# LiBatteryChargeBoostBoard.net
KiCad netlist of a schematic drawn in EAGLE
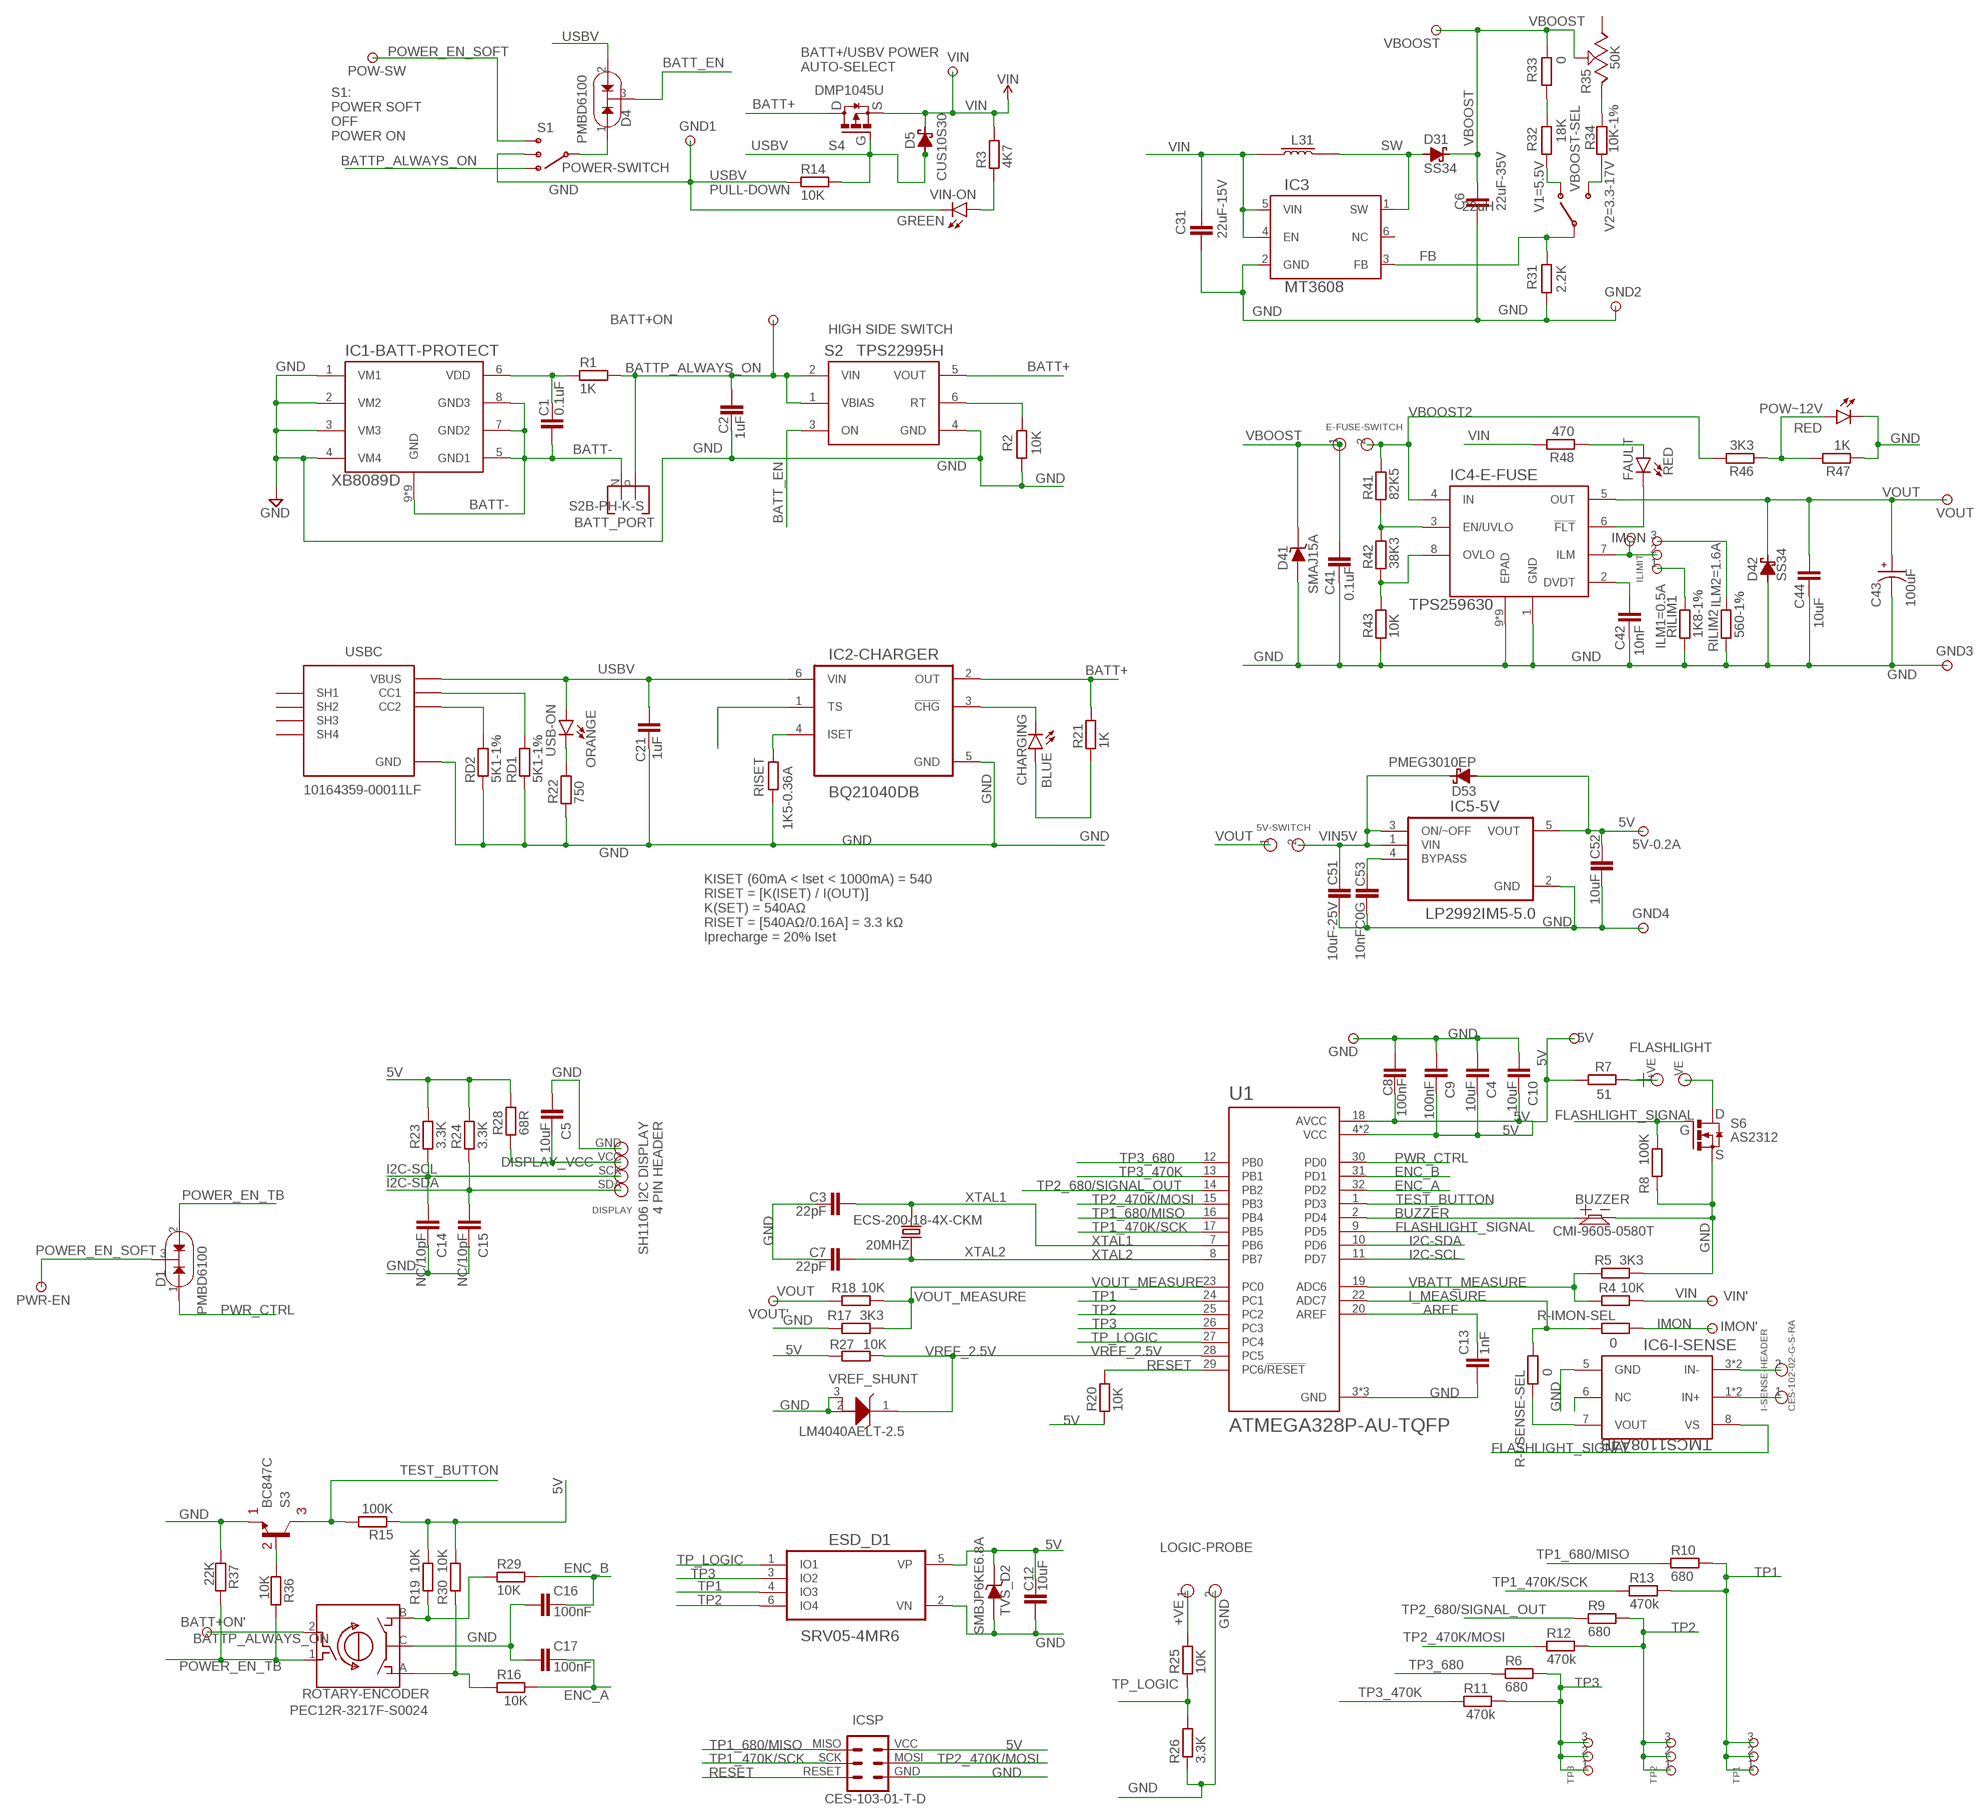
[diagram p0: schematic, sheet 1]

(export (version "E")
  (design (tool "Eeschema 10.0.6"))
  (components
    (comp (ref "5V")
      (value "TEST-POINT-TH")
      (footprint "eagle-import:TEST-POINT-TH-1MM")
      (libsource (lib "eagle-import") (part "TEST-POINT-TH"))
    )
    (comp (ref "5V-0.2A")
      (value "TEST-POINT-TH")
      (footprint "eagle-import:TEST-POINT-TH-1MM")
      (libsource (lib "eagle-import") (part "TEST-POINT-TH"))
    )
    (comp (ref "5V-SWITCH")
      (value "HEADER-2PIN-0.1\"P")
      (footprint "eagle-import:HEADER-2PIN-0.1_P")
      (libsource (lib "eagle-import") (part "HEADER-2PIN-0.1{dblquote}P"))
    )
    (comp (ref "20MHZ")
      (value "ECS-200-18-4X-CKM")
      (footprint "eagle-import:XTAL_ECS-200-18-4X-CKM")
      (fields (field (name "MF") "ECS Inc."))
      (libsource (lib "eagle-import") (part "CRYSTAL-20MHZ-ECS-200-18-4X-CKM"))
    )
    (comp (ref "BATT+ON")
      (value "TEST-POINT-TH")
      (footprint "eagle-import:TEST-POINT-TH-1MM")
      (libsource (lib "eagle-import") (part "TEST-POINT-TH"))
    )
    (comp (ref "BATT+ON'")
      (value "TEST-POINT-TH")
      (footprint "eagle-import:TEST-POINT-TH-1MM")
      (libsource (lib "eagle-import") (part "TEST-POINT-TH"))
    )
    (comp (ref "BATT_PORT")
      (value "S2B-PH-K-S")
      (footprint "eagle-import:S2B-PH-K-S")
      (libsource (lib "eagle-import") (part "S2B-PH-K-S"))
    )
    (comp (ref "BUZZER")
      (value "CMI-9605-0580T")
      (footprint "eagle-import:BUZZER-ACTIVE-CMI-9605-0580T")
      (libsource (lib "eagle-import") (part "BUZZER-ACTIVE-CMI-9605-0580T"))
    )
    (comp (ref "C1")
      (value "0.1uF")
      (footprint "eagle-import:0603")
      (libsource (lib "eagle-import") (part "CAPACITOR_SMD0603"))
    )
    (comp (ref "C2")
      (value "1uF")
      (footprint "eagle-import:0603")
      (libsource (lib "eagle-import") (part "CAPACITOR_SMD0603"))
    )
    (comp (ref "C3")
      (value "22pF")
      (footprint "eagle-import:0603")
      (libsource (lib "eagle-import") (part "CAPACITOR_SMD0603"))
    )
    (comp (ref "C4")
      (value "10uF")
      (footprint "eagle-import:0603")
      (libsource (lib "eagle-import") (part "CAPACITOR_SMD0603"))
    )
    (comp (ref "C5")
      (value "10uF")
      (footprint "eagle-import:1206")
      (libsource (lib "eagle-import") (part "CAPACITOR1206"))
    )
    (comp (ref "C6")
      (value "22uF-35V")
      (footprint "eagle-import:1206")
      (libsource (lib "eagle-import") (part "CAPACITOR_SMD1206"))
    )
    (comp (ref "C7")
      (value "22pF")
      (footprint "eagle-import:0603")
      (libsource (lib "eagle-import") (part "CAPACITOR_SMD0603"))
    )
    (comp (ref "C8")
      (value "100nF")
      (footprint "eagle-import:0603")
      (libsource (lib "eagle-import") (part "CAPACITOR_SMD0603"))
    )
    (comp (ref "C9")
      (value "100nF")
      (footprint "eagle-import:0603")
      (libsource (lib "eagle-import") (part "CAPACITOR_SMD0603"))
    )
    (comp (ref "C10")
      (value "10uF")
      (footprint "eagle-import:0603")
      (libsource (lib "eagle-import") (part "CAPACITOR_SMD0603"))
    )
    (comp (ref "C12")
      (value "10uF")
      (footprint "eagle-import:0603")
      (libsource (lib "eagle-import") (part "CAPACITOR_SMD0603"))
    )
    (comp (ref "C13")
      (value "1nF")
      (footprint "eagle-import:0603")
      (libsource (lib "eagle-import") (part "CAPACITOR_SMD0603"))
    )
    (comp (ref "C14")
      (value "NC/10pF")
      (footprint "eagle-import:0603")
      (libsource (lib "eagle-import") (part "CAPACITOR_SMD0603"))
    )
    (comp (ref "C15")
      (value "NC/10pF")
      (footprint "eagle-import:0603")
      (libsource (lib "eagle-import") (part "CAPACITOR_SMD0603"))
    )
    (comp (ref "C16")
      (value "100nF")
      (footprint "eagle-import:0603")
      (libsource (lib "eagle-import") (part "CAPACITOR_SMD0603"))
    )
    (comp (ref "C17")
      (value "100nF")
      (footprint "eagle-import:0603")
      (libsource (lib "eagle-import") (part "CAPACITOR_SMD0603"))
    )
    (comp (ref "C21")
      (value "1uF")
      (footprint "eagle-import:0603")
      (libsource (lib "eagle-import") (part "CAPACITOR_SMD0603"))
    )
    (comp (ref "C31")
      (value "22uF-15V")
      (footprint "eagle-import:1206")
      (libsource (lib "eagle-import") (part "CAPACITOR_SMD1206"))
    )
    (comp (ref "C41")
      (value "0.1uF")
      (footprint "eagle-import:0603")
      (libsource (lib "eagle-import") (part "CAPACITOR_SMD0603"))
    )
    (comp (ref "C42")
      (value "10nF")
      (footprint "eagle-import:0603")
      (libsource (lib "eagle-import") (part "CAPACITOR_SMD0603"))
    )
    (comp (ref "C43")
      (value "100uF")
      (footprint "eagle-import:CAP_EEEFN1E101UP")
      (fields (field (name "MF") "Panasonic Electronic Components") (field (name "MP") "EEE-FN1E101UP"))
      (libsource (lib "eagle-import") (part "EEEFN1E101UP"))
    )
    (comp (ref "C44")
      (value "10uF")
      (footprint "eagle-import:0603")
      (libsource (lib "eagle-import") (part "CAPACITOR_SMD0603"))
    )
    (comp (ref "C51")
      (value "10uF-25V")
      (footprint "eagle-import:0603")
      (libsource (lib "eagle-import") (part "CAPACITOR0603"))
    )
    (comp (ref "C52")
      (value "10uF")
      (footprint "eagle-import:0603")
      (libsource (lib "eagle-import") (part "CAPACITOR0603"))
    )
    (comp (ref "C53")
      (value "10nFC0G")
      (footprint "eagle-import:0603")
      (libsource (lib "eagle-import") (part "CAPACITOR_SMD0603"))
    )
    (comp (ref "CHARGING")
      (value "BLUE")
      (footprint "eagle-import:0603-DIODE")
      (libsource (lib "eagle-import") (part "LED0603"))
    )
    (comp (ref "D1")
      (value "PMBD6100")
      (footprint "eagle-import:SOT-23-3")
      (libsource (lib "eagle-import") (part "DIODE-DOUBLE-COMMON-CATHODE-PMBD6100,215"))
    )
    (comp (ref "D4")
      (value "PMBD6100")
      (footprint "eagle-import:SOT-23-3")
      (libsource (lib "eagle-import") (part "DIODE-DOUBLE-COMMON-CATHODE-PMBD6100,215"))
    )
    (comp (ref "D5")
      (value "CUS10S30")
      (footprint "eagle-import:SOD-323")
      (libsource (lib "eagle-import") (part "DIODE-SCHOTTKY-CUS10S30,H3F"))
    )
    (comp (ref "D31")
      (value "SS34")
      (footprint "eagle-import:SMA")
      (libsource (lib "eagle-import") (part "DIODE-SCHOTTKY-SS34"))
    )
    (comp (ref "D41")
      (value "SMAJ15A")
      (footprint "eagle-import:SMA")
      (libsource (lib "eagle-import") (part "DIODE-TVS-SMA"))
    )
    (comp (ref "D42")
      (value "SS34")
      (footprint "eagle-import:SMA")
      (libsource (lib "eagle-import") (part "DIODE-SCHOTTKY-SS34"))
    )
    (comp (ref "D53")
      (value "PMEG3010EP")
      (footprint "eagle-import:SOD-128")
      (libsource (lib "eagle-import") (part "DIODE-SCHOTTKY-PMEG3010EP,115"))
    )
    (comp (ref "DISPLAY")
      (value "DISPLAY-1.3\"-SH1106-I2C")
      (footprint "eagle-import:DISPLAY-1.3_-SH1106-I2C")
      (libsource (lib "eagle-import") (part "DISPLAY-1.3{dblquote}-SH1106-I2C"))
    )
    (comp (ref "E-FUSE-SWITCH")
      (value "HEADER-2PIN-0.1\"P")
      (footprint "eagle-import:HEADER-2PIN-0.1_P")
      (libsource (lib "eagle-import") (part "HEADER-2PIN-0.1{dblquote}P"))
    )
    (comp (ref "ESD_D1")
      (value "SRV05-4MR6")
      (footprint "eagle-import:SOT-23-6")
      (fields (field (name "MF") "ON Semiconductor") (field (name "MP") "SRV05-4MR6T1G"))
      (libsource (lib "eagle-import") (part "SRV05-4MR6T1G"))
    )
    (comp (ref "FAULT")
      (value "RED")
      (footprint "eagle-import:0603-DIODE")
      (libsource (lib "eagle-import") (part "LED0603"))
    )
    (comp (ref "FLASHLIGHT")
      (value "HEADER-2PIN-0.2\"P")
      (footprint "eagle-import:HEADER-2PIN-0.2_P")
      (libsource (lib "eagle-import") (part "HEADER-2PIN-0.2{dblquote}P"))
    )
    (comp (ref "GND")
      (value "TEST-POINT-TH")
      (footprint "eagle-import:TEST-POINT-TH-1MM")
      (libsource (lib "eagle-import") (part "TEST-POINT-TH"))
    )
    (comp (ref "GND1")
      (value "TEST-POINT-TH")
      (footprint "eagle-import:TEST-POINT-TH-1MM")
      (libsource (lib "eagle-import") (part "TEST-POINT-TH"))
    )
    (comp (ref "GND2")
      (value "TEST-POINT-TH")
      (footprint "eagle-import:TEST-POINT-TH-1MM")
      (libsource (lib "eagle-import") (part "TEST-POINT-TH"))
    )
    (comp (ref "GND3")
      (value "TEST-POINT-TH")
      (footprint "eagle-import:TEST-POINT-TH-1MM")
      (libsource (lib "eagle-import") (part "TEST-POINT-TH"))
    )
    (comp (ref "GND4")
      (value "TEST-POINT-TH")
      (footprint "eagle-import:TEST-POINT-TH-1MM")
      (libsource (lib "eagle-import") (part "TEST-POINT-TH"))
    )
    (comp (ref "I-SENSE-HEADER")
      (value "CES-102-02-G-S-RA")
      (footprint "eagle-import:HEADER-2PIN-0.1_P")
      (libsource (lib "eagle-import") (part "HEADER-2PIN-0.1{dblquote}P"))
    )
    (comp (ref "IC1-BATT-PROTECT")
      (value "XB8089D")
      (footprint "eagle-import:SOIC-8-POWER-PAD")
      (libsource (lib "eagle-import") (part "XB8089D"))
    )
    (comp (ref "IC2-CHARGER")
      (value "BQ21040DB")
      (footprint "eagle-import:SOT-23-6")
      (fields (field (name "MF") "Texas Instruments") (field (name "MP") "BQ21040DBVR"))
      (libsource (lib "eagle-import") (part "BQ21040DBVR"))
    )
    (comp (ref "IC3")
      (value "MT3608")
      (footprint "eagle-import:SOT-23-6")
      (libsource (lib "eagle-import") (part "MT3608"))
    )
    (comp (ref "IC4-E-FUSE")
      (value "TPS259630")
      (footprint "eagle-import:SOIC-8-POWER-PAD")
      (libsource (lib "eagle-import") (part "TPS259621DDAR"))
    )
    (comp (ref "IC5-5V")
      (value "LP2992IM5-5.0")
      (footprint "eagle-import:SOT-23-5")
      (fields (field (name "MF") "Texas Instruments") (field (name "MP") "LP2992IM5-5.0/NOPB"))
      (libsource (lib "eagle-import") (part "LP2992IM5-5.0"))
    )
    (comp (ref "IC6-I-SENSE")
      (value "TMCS1108A4B")
      (footprint "eagle-import:SOIC-8")
      (libsource (lib "eagle-import") (part "TMCS1108A4B-CURRENT-SENSE"))
    )
    (comp (ref "ICSP")
      (value "CES-103-01-T-D")
      (footprint "eagle-import:HEADER-ICSP-0.1_P")
      (libsource (lib "eagle-import") (part "HEADER-ICSP-0.1{dblquote}P"))
    )
    (comp (ref "ILIMIT")
      (value "HEADER-3PIN-0.1\"P")
      (footprint "eagle-import:HEADER-3PIN-0.1_P")
      (libsource (lib "eagle-import") (part "HEADER-3PIN-0.1{dblquote}P"))
    )
    (comp (ref "IMON")
      (value "TEST-POINT-TH")
      (footprint "eagle-import:TEST-POINT-TH-1MM")
      (libsource (lib "eagle-import") (part "TEST-POINT-TH"))
    )
    (comp (ref "IMON'")
      (value "TEST-POINT-TH")
      (footprint "eagle-import:TEST-POINT-TH-1MM")
      (libsource (lib "eagle-import") (part "TEST-POINT-TH"))
    )
    (comp (ref "L31")
      (value "22uH")
      (footprint "eagle-import:INDUCTOR-SMRH74-220MT")
      (libsource (lib "eagle-import") (part "INDUCTOR-SMRH74-220MT"))
    )
    (comp (ref "LOGIC-PROBE")
      (value "HEADER-2PIN-0.1\"P")
      (footprint "eagle-import:HEADER-2PIN-0.1_P")
      (libsource (lib "eagle-import") (part "HEADER-2PIN-0.1{dblquote}P"))
    )
    (comp (ref "POW-SW")
      (value "TEST-POINT-TH")
      (footprint "eagle-import:TEST-POINT-TH-1MM")
      (libsource (lib "eagle-import") (part "TEST-POINT-TH"))
    )
    (comp (ref "POW~12V")
      (value "RED")
      (footprint "eagle-import:1206-DIODE")
      (libsource (lib "eagle-import") (part "LED1206"))
    )
    (comp (ref "PWR-EN")
      (value "TEST-POINT-TH")
      (footprint "eagle-import:TEST-POINT-TH-1MM")
      (libsource (lib "eagle-import") (part "TEST-POINT-TH"))
    )
    (comp (ref "R-I-SENSE-SEL")
      (value "0")
      (footprint "eagle-import:0603")
      (libsource (lib "eagle-import") (part "RESISTOR_SMD0603"))
    )
    (comp (ref "R-IMON-SEL")
      (value "0")
      (footprint "eagle-import:0603")
      (libsource (lib "eagle-import") (part "RESISTOR_SMD0603"))
    )
    (comp (ref "R1")
      (value "1K")
      (footprint "eagle-import:0603")
      (libsource (lib "eagle-import") (part "RESISTOR_SMD0603"))
    )
    (comp (ref "R2")
      (value "10K")
      (footprint "eagle-import:0603")
      (libsource (lib "eagle-import") (part "RESISTOR_SMD0603"))
    )
    (comp (ref "R3")
      (value "4K7")
      (footprint "eagle-import:0603")
      (libsource (lib "eagle-import") (part "RESISTOR_SMD0603"))
    )
    (comp (ref "R4")
      (value "10K")
      (footprint "eagle-import:0603")
      (libsource (lib "eagle-import") (part "RESISTOR_SMD0603"))
    )
    (comp (ref "R5")
      (value "3K3")
      (footprint "eagle-import:0603")
      (libsource (lib "eagle-import") (part "RESISTOR_SMD0603"))
    )
    (comp (ref "R6")
      (value "680")
      (footprint "eagle-import:1206")
      (libsource (lib "eagle-import") (part "RESISTOR_SMD1206"))
    )
    (comp (ref "R7")
      (value "51")
      (footprint "eagle-import:1206")
      (libsource (lib "eagle-import") (part "RESISTOR_SMD1206"))
    )
    (comp (ref "R8")
      (value "100K")
      (footprint "eagle-import:0603")
      (libsource (lib "eagle-import") (part "RESISTOR_SMD0603"))
    )
    (comp (ref "R9")
      (value "680")
      (footprint "eagle-import:1206")
      (libsource (lib "eagle-import") (part "RESISTOR_SMD1206"))
    )
    (comp (ref "R10")
      (value "680")
      (footprint "eagle-import:1206")
      (libsource (lib "eagle-import") (part "RESISTOR_SMD1206"))
    )
    (comp (ref "R11")
      (value "470k")
      (footprint "eagle-import:1206")
      (libsource (lib "eagle-import") (part "RESISTOR_SMD1206"))
    )
    (comp (ref "R12")
      (value "470k")
      (footprint "eagle-import:1206")
      (libsource (lib "eagle-import") (part "RESISTOR_SMD1206"))
    )
    (comp (ref "R13")
      (value "470k")
      (footprint "eagle-import:1206")
      (libsource (lib "eagle-import") (part "RESISTOR_SMD1206"))
    )
    (comp (ref "R14")
      (value "10K")
      (footprint "eagle-import:0603")
      (libsource (lib "eagle-import") (part "RESISTOR_SMD0603"))
    )
    (comp (ref "R15")
      (value "100K")
      (footprint "eagle-import:0603")
      (libsource (lib "eagle-import") (part "RESISTOR_SMD0603"))
    )
    (comp (ref "R16")
      (value "10K")
      (footprint "eagle-import:0603")
      (libsource (lib "eagle-import") (part "RESISTOR_SMD0603"))
    )
    (comp (ref "R17")
      (value "3K3")
      (footprint "eagle-import:0603")
      (libsource (lib "eagle-import") (part "RESISTOR_SMD0603"))
    )
    (comp (ref "R18")
      (value "10K")
      (footprint "eagle-import:0603")
      (libsource (lib "eagle-import") (part "RESISTOR_SMD0603"))
    )
    (comp (ref "R19")
      (value "10K")
      (footprint "eagle-import:0603")
      (libsource (lib "eagle-import") (part "RESISTOR_SMD0603"))
    )
    (comp (ref "R20")
      (value "10K")
      (footprint "eagle-import:0603")
      (libsource (lib "eagle-import") (part "RESISTOR_SMD0603"))
    )
    (comp (ref "R21")
      (value "1K")
      (footprint "eagle-import:0603")
      (libsource (lib "eagle-import") (part "RESISTOR_SMD0603"))
    )
    (comp (ref "R22")
      (value "750")
      (footprint "eagle-import:0603")
      (libsource (lib "eagle-import") (part "RESISTOR_SMD0603"))
    )
    (comp (ref "R23")
      (value "3.3K")
      (footprint "eagle-import:0603")
      (libsource (lib "eagle-import") (part "RESISTOR_SMD0603"))
    )
    (comp (ref "R24")
      (value "3.3K")
      (footprint "eagle-import:0603")
      (libsource (lib "eagle-import") (part "RESISTOR_SMD0603"))
    )
    (comp (ref "R25")
      (value "10K")
      (footprint "eagle-import:0603")
      (libsource (lib "eagle-import") (part "RESISTOR_SMD0603"))
    )
    (comp (ref "R26")
      (value "3.3K")
      (footprint "eagle-import:0603")
      (libsource (lib "eagle-import") (part "RESISTOR_SMD0603"))
    )
    (comp (ref "R27")
      (value "10K")
      (footprint "eagle-import:0603")
      (libsource (lib "eagle-import") (part "RESISTOR_SMD0603"))
    )
    (comp (ref "R28")
      (value "68R")
      (footprint "eagle-import:0603")
      (libsource (lib "eagle-import") (part "RESISTOR_SMD0603"))
    )
    (comp (ref "R29")
      (value "10K")
      (footprint "eagle-import:0603")
      (libsource (lib "eagle-import") (part "RESISTOR_SMD0603"))
    )
    (comp (ref "R30")
      (value "10K")
      (footprint "eagle-import:0603")
      (libsource (lib "eagle-import") (part "RESISTOR_SMD0603"))
    )
    (comp (ref "R31")
      (value "2.2K")
      (footprint "eagle-import:0603")
      (libsource (lib "eagle-import") (part "RESISTOR_SMD0603"))
    )
    (comp (ref "R32")
      (value "18K")
      (footprint "eagle-import:0603")
      (libsource (lib "eagle-import") (part "RESISTOR_SMD0603"))
    )
    (comp (ref "R33")
      (value "0")
      (footprint "eagle-import:0603")
      (libsource (lib "eagle-import") (part "RESISTOR_SMD0603"))
    )
    (comp (ref "R34")
      (value "10K-1%")
      (footprint "eagle-import:0603")
      (libsource (lib "eagle-import") (part "RESISTOR_SMD0603"))
    )
    (comp (ref "R35")
      (value "50K")
      (footprint "eagle-import:ROTARY-POTENTIOMETER-3386P")
      (libsource (lib "eagle-import") (part "ROTARY-POTENTIOMETER-3386P-1-503TLF"))
    )
    (comp (ref "R36")
      (value "10K")
      (footprint "eagle-import:0603")
      (libsource (lib "eagle-import") (part "RESISTOR_SMD0603"))
    )
    (comp (ref "R37")
      (value "22K")
      (footprint "eagle-import:0603")
      (libsource (lib "eagle-import") (part "RESISTOR_SMD0603"))
    )
    (comp (ref "R41")
      (value "82K5")
      (footprint "eagle-import:0603")
      (libsource (lib "eagle-import") (part "RESISTOR_SMD0603"))
    )
    (comp (ref "R42")
      (value "38K3")
      (footprint "eagle-import:0603")
      (libsource (lib "eagle-import") (part "RESISTOR_SMD0603"))
    )
    (comp (ref "R43")
      (value "10K")
      (footprint "eagle-import:0603")
      (libsource (lib "eagle-import") (part "RESISTOR_SMD0603"))
    )
    (comp (ref "R46")
      (value "3K3")
      (footprint "eagle-import:0603")
      (libsource (lib "eagle-import") (part "RESISTOR_SMD0603"))
    )
    (comp (ref "R47")
      (value "1K")
      (footprint "eagle-import:0603")
      (libsource (lib "eagle-import") (part "RESISTOR_SMD0603"))
    )
    (comp (ref "R48")
      (value "470")
      (footprint "eagle-import:0603")
      (libsource (lib "eagle-import") (part "RESISTOR_SMD0603"))
    )
    (comp (ref "RD1")
      (value "5K1-1%")
      (footprint "eagle-import:0603")
      (libsource (lib "eagle-import") (part "RESISTOR_SMD0603"))
    )
    (comp (ref "RD2")
      (value "5K1-1%")
      (footprint "eagle-import:0603")
      (libsource (lib "eagle-import") (part "RESISTOR_SMD0603"))
    )
    (comp (ref "RILIM1")
      (value "1K8-1%")
      (footprint "eagle-import:0603")
      (libsource (lib "eagle-import") (part "RESISTOR_SMD0603"))
    )
    (comp (ref "RILIM2")
      (value "560-1%")
      (footprint "eagle-import:0603")
      (libsource (lib "eagle-import") (part "RESISTOR_SMD0603"))
    )
    (comp (ref "RISET")
      (value "1K5-0.36A")
      (footprint "eagle-import:0603")
      (libsource (lib "eagle-import") (part "RESISTOR_SMD0603"))
    )
    (comp (ref "ROTARY-ENCODER")
      (value "PEC12R-3217F-S0024")
      (footprint "eagle-import:PEC12R-3217F-S0024")
      (libsource (lib "eagle-import") (part "PEC12R-3217F-S0024"))
    )
    (comp (ref "S1")
      (value "POWER-SWITCH")
      (footprint "eagle-import:CSS-1310MC")
      (libsource (lib "eagle-import") (part "SLIDE-SWITCH-SP3T-VER-TH-MINI"))
    )
    (comp (ref "S2")
      (value "TPS22995H")
      (footprint "eagle-import:SOT-23-6")
      (libsource (lib "eagle-import") (part "TPS22995H-Q1"))
    )
    (comp (ref "S3")
      (value "BC847C")
      (footprint "eagle-import:SOT-23-3")
      (libsource (lib "eagle-import") (part "BC847C"))
    )
    (comp (ref "S4")
      (value "DMP1045U")
      (footprint "eagle-import:SOT-23-3")
      (libsource (lib "eagle-import") (part "DMP1045U"))
    )
    (comp (ref "S6")
      (value "AS2312")
      (footprint "eagle-import:SOT-23-3")
      (libsource (lib "eagle-import") (part "AS2312AS2312"))
    )
    (comp (ref "TP1")
      (value "HEADER-3PIN-0.1\"P")
      (footprint "eagle-import:HEADER-3PIN-0.1_P")
      (libsource (lib "eagle-import") (part "HEADER-3PIN-0.1{dblquote}P"))
    )
    (comp (ref "TP2")
      (value "HEADER-3PIN-0.1\"P")
      (footprint "eagle-import:HEADER-3PIN-0.1_P")
      (libsource (lib "eagle-import") (part "HEADER-3PIN-0.1{dblquote}P"))
    )
    (comp (ref "TP3")
      (value "HEADER-3PIN-0.1\"P")
      (footprint "eagle-import:HEADER-3PIN-0.1_P")
      (libsource (lib "eagle-import") (part "HEADER-3PIN-0.1{dblquote}P"))
    )
    (comp (ref "TVS_D2")
      (value "SMBJP6KE6.8A")
      (footprint "eagle-import:DIOM5336X244N")
      (fields
        (field (name "DIGIKEY_PART_NUMBER") "SMBJP6KE6.8A-TPMSTR-ND")
        (field (name "MF") "Micro Commercial")
        (field (name "MP") "SMBJP6KE6.8A-TP")
      )
      (libsource (lib "eagle-import") (part "SMBJP6KE6.8A-TP"))
    )
    (comp (ref "U1")
      (value "ATMEGA328P-AU-TQFP")
      (footprint "eagle-import:TQFP32")
      (fields (field (name "MF") "Microchip") (field (name "MP") "ATMEGA328P-AU"))
      (libsource (lib "eagle-import") (part "ATMEGA328P-AU-TQFP"))
    )
    (comp (ref "USB-ON")
      (value "ORANGE")
      (footprint "eagle-import:0603-DIODE")
      (libsource (lib "eagle-import") (part "LED0603"))
    )
    (comp (ref "USBC")
      (value "10164359-00011LF")
      (footprint "eagle-import:USB-C-RECEPTABLE-1016435900011LF")
      (fields (field (name "MF") "Amphenol FCI"))
      (libsource (lib "eagle-import") (part "USB-C-RECEPTABLE-10164359-00011LF"))
    )
    (comp (ref "VBOOST")
      (value "TEST-POINT-TH")
      (footprint "eagle-import:TEST-POINT-TH-1MM")
      (libsource (lib "eagle-import") (part "TEST-POINT-TH"))
    )
    (comp (ref "VBOOST-SEL")
      (value "SLIDE-SWITCH-SPDT-VERTICLE-TH")
      (footprint "eagle-import:SLW-883935-2A-D")
      (libsource (lib "eagle-import") (part "SLIDE-SWITCH-SPDT-VERTICLE-TH"))
    )
    (comp (ref "VIN")
      (value "TEST-POINT-TH")
      (footprint "eagle-import:TEST-POINT-TH-1MM")
      (libsource (lib "eagle-import") (part "TEST-POINT-TH"))
    )
    (comp (ref "VIN'")
      (value "TEST-POINT-TH")
      (footprint "eagle-import:TEST-POINT-TH-1MM")
      (libsource (lib "eagle-import") (part "TEST-POINT-TH"))
    )
    (comp (ref "VIN-ON")
      (value "GREEN")
      (footprint "eagle-import:0603-DIODE")
      (libsource (lib "eagle-import") (part "LED0603"))
    )
    (comp (ref "VOUT")
      (value "TEST-POINT-TH")
      (footprint "eagle-import:TEST-POINT-TH-1MM")
      (libsource (lib "eagle-import") (part "TEST-POINT-TH"))
    )
    (comp (ref "VOUT'")
      (value "TEST-POINT-TH")
      (footprint "eagle-import:TEST-POINT-TH-1MM")
      (libsource (lib "eagle-import") (part "TEST-POINT-TH"))
    )
    (comp (ref "VREF_SHUNT")
      (value "LM4040AELT-2.5")
      (footprint "eagle-import:SOT-23-3")
      (libsource (lib "eagle-import") (part "LM4040AELT-2.5-SOT23"))
    )
  )
  (nets
    (net (code "1") (name "/+VE") (class "Default")
      (node (ref "LOGIC-PROBE") (pin "1") (pinfunction "P$1_1") (pintype "bidirectional"))
      (node (ref "R25") (pin "2") (pinfunction "2_2") (pintype "passive"))
    )
    (net (code "2") (name "/5V") (class "Default")
      (node (ref "5V") (pin "P$1") (pinfunction "P$1_P$1") (pintype "bidirectional"))
      (node (ref "5V-0.2A") (pin "P$1") (pinfunction "P$1_P$1") (pintype "bidirectional"))
      (node (ref "C10") (pin "1") (pinfunction "1_1") (pintype "passive"))
      (node (ref "C12") (pin "1") (pinfunction "1_1") (pintype "passive"))
      (node (ref "C4") (pin "1") (pinfunction "1_1") (pintype "passive"))
      (node (ref "C52") (pin "2") (pinfunction "2_2") (pintype "passive"))
      (node (ref "C8") (pin "2") (pinfunction "2_2") (pintype "passive"))
      (node (ref "C9") (pin "1") (pinfunction "1_1") (pintype "passive"))
      (node (ref "D53") (pin "A") (pinfunction "A_A") (pintype "passive"))
      (node (ref "ESD_D1") (pin "5") (pinfunction "VP_5") (pintype "power_in"))
      (node (ref "IC5-5V") (pin "5") (pinfunction "VOUT_5") (pintype "output"))
      (node (ref "ICSP") (pin "VCC") (pinfunction "2_VCC") (pintype "passive"))
      (node (ref "R15") (pin "1") (pinfunction "1_1") (pintype "passive"))
      (node (ref "R19") (pin "2") (pinfunction "2_2") (pintype "passive"))
      (node (ref "R20") (pin "1") (pinfunction "1_1") (pintype "passive"))
      (node (ref "R23") (pin "2") (pinfunction "2_2") (pintype "passive"))
      (node (ref "R24") (pin "2") (pinfunction "2_2") (pintype "passive"))
      (node (ref "R27") (pin "1") (pinfunction "1_1") (pintype "passive"))
      (node (ref "R28") (pin "2") (pinfunction "2_2") (pintype "passive"))
      (node (ref "R30") (pin "2") (pinfunction "2_2") (pintype "passive"))
      (node (ref "R7") (pin "1") (pinfunction "1_1") (pintype "passive"))
      (node (ref "TVS_D2") (pin "C") (pinfunction "C_C") (pintype "passive"))
      (node (ref "U1") (pin "18") (pinfunction "AVCC_18") (pintype "power_in"))
      (node (ref "U1") (pin "4") (pinfunction "VCC_4") (pintype "power_in"))
      (node (ref "U1") (pin "6") (pinfunction "VCC_6") (pintype "power_in"))
    )
    (net (code "3") (name "/AREF") (class "Default")
      (node (ref "C13") (pin "1") (pinfunction "1_1") (pintype "passive"))
      (node (ref "U1") (pin "20") (pinfunction "AREF_20") (pintype "input"))
    )
    (net (code "4") (name "/BATT+") (class "Default")
      (node (ref "IC2-CHARGER") (pin "2") (pinfunction "OUT_2") (pintype "output"))
      (node (ref "R21") (pin "2") (pinfunction "2_2") (pintype "passive"))
      (node (ref "S2") (pin "5") (pinfunction "VOUT_5") (pintype "output"))
      (node (ref "S4") (pin "3") (pinfunction "D_3") (pintype "passive"))
    )
    (net (code "5") (name "/BATT-") (class "Default")
      (node (ref "BATT_PORT") (pin "N") (pinfunction "N_N") (pintype "bidirectional"))
      (node (ref "C1") (pin "2") (pinfunction "2_2") (pintype "passive"))
      (node (ref "IC1-BATT-PROTECT") (pin "10") (pinfunction "GND_10") (pintype "power_in"))
      (node (ref "IC1-BATT-PROTECT") (pin "11") (pinfunction "GND_11") (pintype "power_in"))
      (node (ref "IC1-BATT-PROTECT") (pin "12") (pinfunction "GND_12") (pintype "power_in"))
      (node (ref "IC1-BATT-PROTECT") (pin "13") (pinfunction "GND_13") (pintype "power_in"))
      (node (ref "IC1-BATT-PROTECT") (pin "14") (pinfunction "GND_14") (pintype "power_in"))
      (node (ref "IC1-BATT-PROTECT") (pin "15") (pinfunction "GND_15") (pintype "power_in"))
      (node (ref "IC1-BATT-PROTECT") (pin "16") (pinfunction "GND_16") (pintype "power_in"))
      (node (ref "IC1-BATT-PROTECT") (pin "17") (pinfunction "GND_17") (pintype "power_in"))
      (node (ref "IC1-BATT-PROTECT") (pin "5") (pinfunction "GND1_5") (pintype "power_in"))
      (node (ref "IC1-BATT-PROTECT") (pin "7") (pinfunction "GND2_7") (pintype "power_in"))
      (node (ref "IC1-BATT-PROTECT") (pin "8") (pinfunction "GND3_8") (pintype "power_in"))
      (node (ref "IC1-BATT-PROTECT") (pin "9") (pinfunction "GND_9") (pintype "power_in"))
    )
    (net (code "6") (name "/BATTP_ALWAYS_ON") (class "Default")
      (node (ref "BATT+ON") (pin "P$1") (pinfunction "P$1_P$1") (pintype "bidirectional"))
      (node (ref "BATT+ON'") (pin "P$1") (pinfunction "P$1_P$1") (pintype "bidirectional"))
      (node (ref "BATT_PORT") (pin "P") (pinfunction "P_P") (pintype "bidirectional"))
      (node (ref "C2") (pin "2") (pinfunction "2_2") (pintype "passive"))
      (node (ref "R1") (pin "2") (pinfunction "2_2") (pintype "passive"))
      (node (ref "ROTARY-ENCODER") (pin "2") (pinfunction "2_2") (pintype "bidirectional"))
      (node (ref "S1") (pin "1") (pinfunction "1_1") (pintype "bidirectional"))
      (node (ref "S2") (pin "1") (pinfunction "VBIAS_1") (pintype "output"))
      (node (ref "S2") (pin "2") (pinfunction "VIN_2") (pintype "input"))
    )
    (net (code "7") (name "/BATT_EN") (class "Default")
      (node (ref "D4") (pin "3") (pinfunction "C_3") (pintype "bidirectional"))
      (node (ref "S2") (pin "3") (pinfunction "ON_3") (pintype "input"))
    )
    (net (code "8") (name "/BUZZER") (class "Default")
      (node (ref "BUZZER") (pin "P$1") (pinfunction "P$1_P$1") (pintype "bidirectional"))
      (node (ref "U1") (pin "2") (pinfunction "PD4_2") (pintype "bidirectional"))
    )
    (net (code "9") (name "/DISPLAY_VCC") (class "Default")
      (node (ref "C5") (pin "1") (pinfunction "1_1") (pintype "passive"))
      (node (ref "DISPLAY") (pin "VCC") (pinfunction "VCC_VCC") (pintype "bidirectional"))
      (node (ref "R28") (pin "1") (pinfunction "1_1") (pintype "passive"))
    )
    (net (code "10") (name "/ENC_A") (class "Default")
      (node (ref "C17") (pin "1") (pinfunction "1_1") (pintype "passive"))
      (node (ref "R16") (pin "2") (pinfunction "2_2") (pintype "passive"))
      (node (ref "U1") (pin "32") (pinfunction "PD2_32") (pintype "bidirectional"))
    )
    (net (code "11") (name "/ENC_B") (class "Default")
      (node (ref "C16") (pin "1") (pinfunction "1_1") (pintype "passive"))
      (node (ref "R29") (pin "2") (pinfunction "2_2") (pintype "passive"))
      (node (ref "U1") (pin "31") (pinfunction "PD1_31") (pintype "bidirectional"))
    )
    (net (code "12") (name "/FB") (class "Default")
      (node (ref "IC3") (pin "3") (pinfunction "FB_3") (pintype "power_in"))
      (node (ref "R31") (pin "1") (pinfunction "1_1") (pintype "passive"))
      (node (ref "VBOOST-SEL") (pin "C") (pinfunction "C_C") (pintype "bidirectional"))
    )
    (net (code "13") (name "/FLASHLIGHT_SIGNAL") (class "Default")
      (node (ref "IC6-I-SENSE") (pin "8") (pinfunction "VS_8") (pintype "input"))
      (node (ref "R8") (pin "1") (pinfunction "1_1") (pintype "passive"))
      (node (ref "S6") (pin "1") (pinfunction "G_1") (pintype "passive"))
      (node (ref "U1") (pin "9") (pinfunction "PD5_9") (pintype "bidirectional"))
    )
    (net (code "14") (name "/I2C-SCL") (class "Default")
      (node (ref "C14") (pin "2") (pinfunction "2_2") (pintype "passive"))
      (node (ref "DISPLAY") (pin "SCK") (pinfunction "SCK_SCK") (pintype "bidirectional"))
      (node (ref "R23") (pin "1") (pinfunction "1_1") (pintype "passive"))
      (node (ref "U1") (pin "11") (pinfunction "PD7_11") (pintype "bidirectional"))
    )
    (net (code "15") (name "/I2C-SDA") (class "Default")
      (node (ref "C15") (pin "2") (pinfunction "2_2") (pintype "passive"))
      (node (ref "DISPLAY") (pin "SDA") (pinfunction "SDA_SDA") (pintype "bidirectional"))
      (node (ref "R24") (pin "1") (pinfunction "1_1") (pintype "passive"))
      (node (ref "U1") (pin "10") (pinfunction "PD6_10") (pintype "bidirectional"))
    )
    (net (code "16") (name "/IMON") (class "Default")
      (node (ref "IC4-E-FUSE") (pin "7") (pinfunction "ILM_7") (pintype "input"))
      (node (ref "ILIMIT") (pin "2") (pinfunction "P$2_2") (pintype "bidirectional"))
      (node (ref "IMON") (pin "P$1") (pinfunction "P$1_P$1") (pintype "bidirectional"))
      (node (ref "IMON'") (pin "P$1") (pinfunction "P$1_P$1") (pintype "bidirectional"))
      (node (ref "R-IMON-SEL") (pin "1") (pinfunction "1_1") (pintype "passive"))
    )
    (net (code "17") (name "/I_MEASURE") (class "Default")
      (node (ref "R-I-SENSE-SEL") (pin "1") (pinfunction "1_1") (pintype "passive"))
      (node (ref "R-IMON-SEL") (pin "2") (pinfunction "2_2") (pintype "passive"))
      (node (ref "U1") (pin "22") (pinfunction "ADC7_22") (pintype "bidirectional"))
    )
    (net (code "18") (name "/POWER_EN_SOFT") (class "Default")
      (node (ref "D1") (pin "3") (pinfunction "C_3") (pintype "bidirectional"))
      (node (ref "POW-SW") (pin "P$1") (pinfunction "P$1_P$1") (pintype "bidirectional"))
      (node (ref "PWR-EN") (pin "P$1") (pinfunction "P$1_P$1") (pintype "bidirectional"))
      (node (ref "S1") (pin "3") (pinfunction "3_3") (pintype "bidirectional"))
    )
    (net (code "19") (name "/POWER_EN_TB") (class "Default")
      (node (ref "D1") (pin "2") (pinfunction "A2_2") (pintype "bidirectional"))
      (node (ref "R36") (pin "2") (pinfunction "2_2") (pintype "passive"))
      (node (ref "R37") (pin "2") (pinfunction "2_2") (pintype "passive"))
      (node (ref "ROTARY-ENCODER") (pin "1") (pinfunction "1_1") (pintype "bidirectional"))
    )
    (net (code "20") (name "/PWR_CTRL") (class "Default")
      (node (ref "D1") (pin "1") (pinfunction "A1_1") (pintype "bidirectional"))
      (node (ref "U1") (pin "30") (pinfunction "PD0_30") (pintype "bidirectional"))
    )
    (net (code "21") (name "/RESET") (class "Default")
      (node (ref "ICSP") (pin "RESET") (pinfunction "5_RESET") (pintype "passive"))
      (node (ref "R20") (pin "2") (pinfunction "2_2") (pintype "passive"))
      (node (ref "U1") (pin "29") (pinfunction "PC6/~{RESET}_29") (pintype "bidirectional"))
    )
    (net (code "22") (name "/SW") (class "Default")
      (node (ref "D31") (pin "A") (pinfunction "A_A") (pintype "passive"))
      (node (ref "IC3") (pin "1") (pinfunction "SW_1") (pintype "output"))
      (node (ref "L31") (pin "P$2") (pinfunction "P$2_P$2") (pintype "bidirectional"))
    )
    (net (code "23") (name "/TEST_BUTTON") (class "Default")
      (node (ref "R15") (pin "2") (pinfunction "2_2") (pintype "passive"))
      (node (ref "S3") (pin "3") (pinfunction "C_3") (pintype "passive"))
      (node (ref "U1") (pin "1") (pinfunction "PD3_1") (pintype "bidirectional"))
    )
    (net (code "24") (name "/TP1") (class "Default")
      (node (ref "ESD_D1") (pin "4") (pinfunction "IO3_4") (pintype "input"))
      (node (ref "R10") (pin "2") (pinfunction "2_2") (pintype "passive"))
      (node (ref "R13") (pin "2") (pinfunction "2_2") (pintype "passive"))
      (node (ref "TP1") (pin "1") (pinfunction "P$1_1") (pintype "bidirectional"))
      (node (ref "TP1") (pin "2") (pinfunction "P$2_2") (pintype "bidirectional"))
      (node (ref "TP1") (pin "3") (pinfunction "P$3_3") (pintype "bidirectional"))
      (node (ref "U1") (pin "24") (pinfunction "PC1_24") (pintype "bidirectional"))
    )
    (net (code "25") (name "/TP1_470K{slash}SCK") (class "Default")
      (node (ref "ICSP") (pin "SCK") (pinfunction "3_SCK") (pintype "passive"))
      (node (ref "R13") (pin "1") (pinfunction "1_1") (pintype "passive"))
      (node (ref "U1") (pin "17") (pinfunction "PB5_17") (pintype "bidirectional"))
    )
    (net (code "26") (name "/TP1_680{slash}MISO") (class "Default")
      (node (ref "ICSP") (pin "MISO") (pinfunction "1_MISO") (pintype "passive"))
      (node (ref "R10") (pin "1") (pinfunction "1_1") (pintype "passive"))
      (node (ref "U1") (pin "16") (pinfunction "PB4_16") (pintype "bidirectional"))
    )
    (net (code "27") (name "/TP2") (class "Default")
      (node (ref "ESD_D1") (pin "6") (pinfunction "IO4_6") (pintype "input"))
      (node (ref "R12") (pin "2") (pinfunction "2_2") (pintype "passive"))
      (node (ref "R9") (pin "2") (pinfunction "2_2") (pintype "passive"))
      (node (ref "TP2") (pin "1") (pinfunction "P$1_1") (pintype "bidirectional"))
      (node (ref "TP2") (pin "2") (pinfunction "P$2_2") (pintype "bidirectional"))
      (node (ref "TP2") (pin "3") (pinfunction "P$3_3") (pintype "bidirectional"))
      (node (ref "U1") (pin "25") (pinfunction "PC2_25") (pintype "bidirectional"))
    )
    (net (code "28") (name "/TP2_470K{slash}MOSI") (class "Default")
      (node (ref "ICSP") (pin "MOSI") (pinfunction "4_MOSI") (pintype "passive"))
      (node (ref "R12") (pin "1") (pinfunction "1_1") (pintype "passive"))
      (node (ref "U1") (pin "15") (pinfunction "PB3_15") (pintype "bidirectional"))
    )
    (net (code "29") (name "/TP2_680{slash}SIGNAL_OUT") (class "Default")
      (node (ref "R9") (pin "1") (pinfunction "1_1") (pintype "passive"))
      (node (ref "U1") (pin "14") (pinfunction "PB2_14") (pintype "bidirectional"))
    )
    (net (code "30") (name "/TP3") (class "Default")
      (node (ref "ESD_D1") (pin "3") (pinfunction "IO2_3") (pintype "input"))
      (node (ref "R11") (pin "2") (pinfunction "2_2") (pintype "passive"))
      (node (ref "R6") (pin "2") (pinfunction "2_2") (pintype "passive"))
      (node (ref "TP3") (pin "1") (pinfunction "P$1_1") (pintype "bidirectional"))
      (node (ref "TP3") (pin "2") (pinfunction "P$2_2") (pintype "bidirectional"))
      (node (ref "TP3") (pin "3") (pinfunction "P$3_3") (pintype "bidirectional"))
      (node (ref "U1") (pin "26") (pinfunction "PC3_26") (pintype "bidirectional"))
    )
    (net (code "31") (name "/TP3_470K") (class "Default")
      (node (ref "R11") (pin "1") (pinfunction "1_1") (pintype "passive"))
      (node (ref "U1") (pin "13") (pinfunction "PB1_13") (pintype "bidirectional"))
    )
    (net (code "32") (name "/TP3_680") (class "Default")
      (node (ref "R6") (pin "1") (pinfunction "1_1") (pintype "passive"))
      (node (ref "U1") (pin "12") (pinfunction "PB0_12") (pintype "bidirectional"))
    )
    (net (code "33") (name "/TP_LOGIC") (class "Default")
      (node (ref "ESD_D1") (pin "1") (pinfunction "IO1_1") (pintype "input"))
      (node (ref "R25") (pin "1") (pinfunction "1_1") (pintype "passive"))
      (node (ref "R26") (pin "2") (pinfunction "2_2") (pintype "passive"))
      (node (ref "U1") (pin "27") (pinfunction "PC4_27") (pintype "bidirectional"))
    )
    (net (code "34") (name "/USBV") (class "Default")
      (node (ref "C21") (pin "2") (pinfunction "2_2") (pintype "passive"))
      (node (ref "D4") (pin "2") (pinfunction "A2_2") (pintype "bidirectional"))
      (node (ref "D5") (pin "A") (pinfunction "A_A") (pintype "passive"))
      (node (ref "IC2-CHARGER") (pin "6") (pinfunction "VIN_6") (pintype "input"))
      (node (ref "R14") (pin "2") (pinfunction "2_2") (pintype "passive"))
      (node (ref "S4") (pin "1") (pinfunction "G_1") (pintype "passive"))
      (node (ref "USB-ON") (pin "A") (pinfunction "A_A") (pintype "passive"))
      (node (ref "USBC") (pin "A9") (pinfunction "VBUS_A9") (pintype "power_in"))
      (node (ref "USBC") (pin "B9") (pinfunction "VBUS_B9") (pintype "power_in"))
    )
    (net (code "35") (name "/VBATT_MEASURE") (class "Default")
      (node (ref "R4") (pin "2") (pinfunction "2_2") (pintype "passive"))
      (node (ref "R5") (pin "1") (pinfunction "1_1") (pintype "passive"))
      (node (ref "U1") (pin "19") (pinfunction "ADC6_19") (pintype "bidirectional"))
    )
    (net (code "36") (name "/VBOOST") (class "Default")
      (node (ref "C41") (pin "2") (pinfunction "2_2") (pintype "passive"))
      (node (ref "C6") (pin "2") (pinfunction "2_2") (pintype "passive"))
      (node (ref "D31") (pin "C") (pinfunction "C_C") (pintype "passive"))
      (node (ref "D41") (pin "C") (pinfunction "C_C") (pintype "passive"))
      (node (ref "E-FUSE-SWITCH") (pin "1") (pinfunction "P$1_1") (pintype "bidirectional"))
      (node (ref "R33") (pin "1") (pinfunction "1_1") (pintype "passive"))
      (node (ref "R35") (pin "2") (pinfunction "S_2") (pintype "passive"))
      (node (ref "VBOOST") (pin "P$1") (pinfunction "P$1_P$1") (pintype "bidirectional"))
    )
    (net (code "37") (name "/VBOOST2") (class "Default")
      (node (ref "E-FUSE-SWITCH") (pin "2") (pinfunction "P$2_2") (pintype "bidirectional"))
      (node (ref "IC4-E-FUSE") (pin "4") (pinfunction "IN_4") (pintype "input"))
      (node (ref "R41") (pin "2") (pinfunction "2_2") (pintype "passive"))
      (node (ref "R46") (pin "2") (pinfunction "2_2") (pintype "passive"))
    )
    (net (code "38") (name "/VIN5V") (class "Default")
      (node (ref "5V-SWITCH") (pin "2") (pinfunction "P$2_2") (pintype "bidirectional"))
      (node (ref "C51") (pin "2") (pinfunction "2_2") (pintype "passive"))
      (node (ref "D53") (pin "K") (pinfunction "C_K") (pintype "passive"))
      (node (ref "IC5-5V") (pin "1") (pinfunction "VIN_1") (pintype "input"))
      (node (ref "IC5-5V") (pin "3") (pinfunction "ON/~{OFF}_3") (pintype "input"))
    )
    (net (code "39") (name "/VOUT") (class "Default")
      (node (ref "5V-SWITCH") (pin "1") (pinfunction "P$1_1") (pintype "bidirectional"))
      (node (ref "C43") (pin "1") (pinfunction "1_1") (pintype "passive"))
      (node (ref "C44") (pin "2") (pinfunction "2_2") (pintype "passive"))
      (node (ref "D42") (pin "C") (pinfunction "C_C") (pintype "passive"))
      (node (ref "IC4-E-FUSE") (pin "5") (pinfunction "OUT_5") (pintype "output"))
      (node (ref "R18") (pin "2") (pinfunction "2_2") (pintype "passive"))
      (node (ref "VOUT") (pin "P$1") (pinfunction "P$1_P$1") (pintype "bidirectional"))
      (node (ref "VOUT'") (pin "P$1") (pinfunction "P$1_P$1") (pintype "bidirectional"))
    )
    (net (code "40") (name "/VOUT_MEASURE") (class "Default")
      (node (ref "R17") (pin "2") (pinfunction "2_2") (pintype "passive"))
      (node (ref "R18") (pin "1") (pinfunction "1_1") (pintype "passive"))
      (node (ref "U1") (pin "23") (pinfunction "PC0_23") (pintype "bidirectional"))
    )
    (net (code "41") (name "/VREF_2.5V") (class "Default")
      (node (ref "R27") (pin "2") (pinfunction "2_2") (pintype "passive"))
      (node (ref "U1") (pin "28") (pinfunction "PC5_28") (pintype "bidirectional"))
      (node (ref "VREF_SHUNT") (pin "1") (pinfunction "C_1") (pintype "bidirectional"))
    )
    (net (code "42") (name "/XTAL1") (class "Default")
      (node (ref "20MHZ") (pin "2") (pinfunction "2_2") (pintype "passive"))
      (node (ref "C3") (pin "2") (pinfunction "2_2") (pintype "passive"))
      (node (ref "U1") (pin "7") (pinfunction "PB6_7") (pintype "bidirectional"))
    )
    (net (code "43") (name "/XTAL2") (class "Default")
      (node (ref "20MHZ") (pin "1") (pinfunction "1_1") (pintype "passive"))
      (node (ref "C7") (pin "2") (pinfunction "2_2") (pintype "passive"))
      (node (ref "U1") (pin "8") (pinfunction "PB7_8") (pintype "bidirectional"))
    )
    (net (code "44") (name "GND") (class "Default")
      (node (ref "BUZZER") (pin "P$2") (pinfunction "P$2_P$2") (pintype "bidirectional"))
      (node (ref "C10") (pin "2") (pinfunction "2_2") (pintype "passive"))
      (node (ref "C12") (pin "2") (pinfunction "2_2") (pintype "passive"))
      (node (ref "C13") (pin "2") (pinfunction "2_2") (pintype "passive"))
      (node (ref "C14") (pin "1") (pinfunction "1_1") (pintype "passive"))
      (node (ref "C15") (pin "1") (pinfunction "1_1") (pintype "passive"))
      (node (ref "C16") (pin "2") (pinfunction "2_2") (pintype "passive"))
      (node (ref "C17") (pin "2") (pinfunction "2_2") (pintype "passive"))
      (node (ref "C2") (pin "1") (pinfunction "1_1") (pintype "passive"))
      (node (ref "C21") (pin "1") (pinfunction "1_1") (pintype "passive"))
      (node (ref "C3") (pin "1") (pinfunction "1_1") (pintype "passive"))
      (node (ref "C31") (pin "1") (pinfunction "1_1") (pintype "passive"))
      (node (ref "C4") (pin "2") (pinfunction "2_2") (pintype "passive"))
      (node (ref "C41") (pin "1") (pinfunction "1_1") (pintype "passive"))
      (node (ref "C42") (pin "1") (pinfunction "1_1") (pintype "passive"))
      (node (ref "C43") (pin "2") (pinfunction "2_2") (pintype "passive"))
      (node (ref "C44") (pin "1") (pinfunction "1_1") (pintype "passive"))
      (node (ref "C5") (pin "2") (pinfunction "2_2") (pintype "passive"))
      (node (ref "C51") (pin "1") (pinfunction "1_1") (pintype "passive"))
      (node (ref "C52") (pin "1") (pinfunction "1_1") (pintype "passive"))
      (node (ref "C53") (pin "1") (pinfunction "1_1") (pintype "passive"))
      (node (ref "C6") (pin "1") (pinfunction "1_1") (pintype "passive"))
      (node (ref "C7") (pin "1") (pinfunction "1_1") (pintype "passive"))
      (node (ref "C8") (pin "1") (pinfunction "1_1") (pintype "passive"))
      (node (ref "C9") (pin "2") (pinfunction "2_2") (pintype "passive"))
      (node (ref "D41") (pin "A") (pinfunction "A_A") (pintype "passive"))
      (node (ref "D42") (pin "A") (pinfunction "A_A") (pintype "passive"))
      (node (ref "DISPLAY") (pin "GND") (pinfunction "GND_GND") (pintype "bidirectional"))
      (node (ref "ESD_D1") (pin "2") (pinfunction "VN_2") (pintype "power_in"))
      (node (ref "GND") (pin "P$1") (pinfunction "P$1_P$1") (pintype "bidirectional"))
      (node (ref "GND1") (pin "P$1") (pinfunction "P$1_P$1") (pintype "bidirectional"))
      (node (ref "GND2") (pin "P$1") (pinfunction "P$1_P$1") (pintype "bidirectional"))
      (node (ref "GND3") (pin "P$1") (pinfunction "P$1_P$1") (pintype "bidirectional"))
      (node (ref "GND4") (pin "P$1") (pinfunction "P$1_P$1") (pintype "bidirectional"))
      (node (ref "IC1-BATT-PROTECT") (pin "1") (pinfunction "VM1_1") (pintype "power_in"))
      (node (ref "IC1-BATT-PROTECT") (pin "2") (pinfunction "VM2_2") (pintype "power_in"))
      (node (ref "IC1-BATT-PROTECT") (pin "3") (pinfunction "VM3_3") (pintype "power_in"))
      (node (ref "IC1-BATT-PROTECT") (pin "4") (pinfunction "VM4_4") (pintype "power_in"))
      (node (ref "IC2-CHARGER") (pin "5") (pinfunction "GND_5") (pintype "power_in"))
      (node (ref "IC3") (pin "2") (pinfunction "GND_2") (pintype "input"))
      (node (ref "IC4-E-FUSE") (pin "1") (pinfunction "GND_1") (pintype "power_in"))
      (node (ref "IC4-E-FUSE") (pin "10") (pinfunction "EPAD_10") (pintype "power_in"))
      (node (ref "IC4-E-FUSE") (pin "11") (pinfunction "EPAD_11") (pintype "power_in"))
      (node (ref "IC4-E-FUSE") (pin "12") (pinfunction "EPAD_12") (pintype "power_in"))
      (node (ref "IC4-E-FUSE") (pin "13") (pinfunction "EPAD_13") (pintype "power_in"))
      (node (ref "IC4-E-FUSE") (pin "14") (pinfunction "EPAD_14") (pintype "power_in"))
      (node (ref "IC4-E-FUSE") (pin "15") (pinfunction "EPAD_15") (pintype "power_in"))
      (node (ref "IC4-E-FUSE") (pin "16") (pinfunction "EPAD_16") (pintype "power_in"))
      (node (ref "IC4-E-FUSE") (pin "17") (pinfunction "EPAD_17") (pintype "power_in"))
      (node (ref "IC4-E-FUSE") (pin "9") (pinfunction "EPAD_9") (pintype "power_in"))
      (node (ref "IC5-5V") (pin "2") (pinfunction "GND_2") (pintype "power_in"))
      (node (ref "IC6-I-SENSE") (pin "5") (pinfunction "GND_5") (pintype "power_in"))
      (node (ref "ICSP") (pin "GND") (pinfunction "6_GND") (pintype "passive"))
      (node (ref "LOGIC-PROBE") (pin "2") (pinfunction "P$2_2") (pintype "bidirectional"))
      (node (ref "POW~12V") (pin "C") (pinfunction "C_C") (pintype "passive"))
      (node (ref "R14") (pin "1") (pinfunction "1_1") (pintype "passive"))
      (node (ref "R17") (pin "1") (pinfunction "1_1") (pintype "passive"))
      (node (ref "R2") (pin "2") (pinfunction "2_2") (pintype "passive"))
      (node (ref "R22") (pin "1") (pinfunction "1_1") (pintype "passive"))
      (node (ref "R26") (pin "1") (pinfunction "1_1") (pintype "passive"))
      (node (ref "R31") (pin "2") (pinfunction "2_2") (pintype "passive"))
      (node (ref "R37") (pin "1") (pinfunction "1_1") (pintype "passive"))
      (node (ref "R43") (pin "1") (pinfunction "1_1") (pintype "passive"))
      (node (ref "R47") (pin "1") (pinfunction "1_1") (pintype "passive"))
      (node (ref "R5") (pin "2") (pinfunction "2_2") (pintype "passive"))
      (node (ref "R8") (pin "2") (pinfunction "2_2") (pintype "passive"))
      (node (ref "RD1") (pin "1") (pinfunction "1_1") (pintype "passive"))
      (node (ref "RD2") (pin "1") (pinfunction "1_1") (pintype "passive"))
      (node (ref "RILIM1") (pin "1") (pinfunction "1_1") (pintype "passive"))
      (node (ref "RILIM2") (pin "1") (pinfunction "1_1") (pintype "passive"))
      (node (ref "RISET") (pin "2") (pinfunction "2_2") (pintype "passive"))
      (node (ref "ROTARY-ENCODER") (pin "C") (pinfunction "C_C") (pintype "bidirectional"))
      (node (ref "S1") (pin "2") (pinfunction "2_2") (pintype "bidirectional"))
      (node (ref "S2") (pin "4") (pinfunction "GND_4") (pintype "power_in"))
      (node (ref "S3") (pin "2") (pinfunction "E_2") (pintype "passive"))
      (node (ref "S6") (pin "2") (pinfunction "S_2") (pintype "passive"))
      (node (ref "TVS_D2") (pin "A") (pinfunction "A_A") (pintype "passive"))
      (node (ref "U1") (pin "21") (pinfunction "GND_21") (pintype "power_in"))
      (node (ref "U1") (pin "3") (pinfunction "GND_3") (pintype "power_in"))
      (node (ref "U1") (pin "5") (pinfunction "GND_5") (pintype "power_in"))
      (node (ref "USBC") (pin "A12") (pinfunction "GND_A12") (pintype "bidirectional"))
      (node (ref "USBC") (pin "B12") (pinfunction "GND_B12") (pintype "bidirectional"))
      (node (ref "VIN-ON") (pin "C") (pinfunction "C_C") (pintype "passive"))
      (node (ref "VREF_SHUNT") (pin "2") (pinfunction "A_2") (pintype "bidirectional"))
      (node (ref "VREF_SHUNT") (pin "3") (pinfunction "NC/A_3") (pintype "bidirectional"))
    )
    (net (code "45") (name "Net-(CHARGING-PadA)") (class "Default")
      (node (ref "CHARGING") (pin "A") (pinfunction "A_A") (pintype "passive"))
      (node (ref "R21") (pin "1") (pinfunction "1_1") (pintype "passive"))
    )
    (net (code "46") (name "Net-(D4-A1)") (class "Default")
      (node (ref "D4") (pin "1") (pinfunction "A1_1") (pintype "bidirectional"))
      (node (ref "S1") (pin "C") (pinfunction "C_C") (pintype "bidirectional"))
    )
    (net (code "47") (name "Net-(FAULT-PadA)") (class "Default")
      (node (ref "FAULT") (pin "A") (pinfunction "A_A") (pintype "passive"))
      (node (ref "R48") (pin "1") (pinfunction "1_1") (pintype "passive"))
    )
    (net (code "48") (name "Net-(FLASHLIGHT-P$1)") (class "Default")
      (node (ref "FLASHLIGHT") (pin "+VE") (pinfunction "P$1_+VE") (pintype "bidirectional"))
      (node (ref "R7") (pin "2") (pinfunction "2_2") (pintype "passive"))
    )
    (net (code "49") (name "Net-(FLASHLIGHT-P$2)") (class "Default")
      (node (ref "FLASHLIGHT") (pin "-VE") (pinfunction "P$2_-VE") (pintype "bidirectional"))
      (node (ref "S6") (pin "3") (pinfunction "D_3") (pintype "passive"))
    )
    (net (code "50") (name "Net-(I-SENSE-HEADER-P$1)") (class "Default")
      (node (ref "I-SENSE-HEADER") (pin "1") (pinfunction "P$1_1") (pintype "bidirectional"))
      (node (ref "IC6-I-SENSE") (pin "1") (pinfunction "IN+_1") (pintype "input"))
      (node (ref "IC6-I-SENSE") (pin "2") (pinfunction "IN+_2") (pintype "input"))
    )
    (net (code "51") (name "Net-(I-SENSE-HEADER-P$2)") (class "Default")
      (node (ref "I-SENSE-HEADER") (pin "2") (pinfunction "P$2_2") (pintype "bidirectional"))
      (node (ref "IC6-I-SENSE") (pin "3") (pinfunction "IN-_3") (pintype "output"))
      (node (ref "IC6-I-SENSE") (pin "4") (pinfunction "IN-_4") (pintype "output"))
    )
    (net (code "52") (name "Net-(IC1-BATT-PROTECT-VDD)") (class "Default")
      (node (ref "C1") (pin "1") (pinfunction "1_1") (pintype "passive"))
      (node (ref "IC1-BATT-PROTECT") (pin "6") (pinfunction "VDD_6") (pintype "power_in"))
      (node (ref "R1") (pin "1") (pinfunction "1_1") (pintype "passive"))
    )
    (net (code "53") (name "Net-(IC2-CHARGER-ISET)") (class "Default")
      (node (ref "IC2-CHARGER") (pin "4") (pinfunction "ISET_4") (pintype "input"))
      (node (ref "RISET") (pin "1") (pinfunction "1_1") (pintype "passive"))
    )
    (net (code "54") (name "Net-(IC2-CHARGER-~{CHG})") (class "Default")
      (node (ref "CHARGING") (pin "C") (pinfunction "C_C") (pintype "passive"))
      (node (ref "IC2-CHARGER") (pin "3") (pinfunction "~{CHG}_3") (pintype "output"))
    )
    (net (code "55") (name "Net-(IC4-E-FUSE-DVDT)") (class "Default")
      (node (ref "C42") (pin "2") (pinfunction "2_2") (pintype "passive"))
      (node (ref "IC4-E-FUSE") (pin "2") (pinfunction "DVDT_2") (pintype "input"))
    )
    (net (code "56") (name "Net-(IC4-E-FUSE-EN{slash}UVLO)") (class "Default")
      (node (ref "IC4-E-FUSE") (pin "3") (pinfunction "EN/UVLO_3") (pintype "input"))
      (node (ref "R41") (pin "1") (pinfunction "1_1") (pintype "passive"))
      (node (ref "R42") (pin "2") (pinfunction "2_2") (pintype "passive"))
    )
    (net (code "57") (name "Net-(IC4-E-FUSE-OVLO)") (class "Default")
      (node (ref "IC4-E-FUSE") (pin "8") (pinfunction "OVLO_8") (pintype "output"))
      (node (ref "R42") (pin "1") (pinfunction "1_1") (pintype "passive"))
      (node (ref "R43") (pin "2") (pinfunction "2_2") (pintype "passive"))
    )
    (net (code "58") (name "Net-(IC4-E-FUSE-~{FLT})") (class "Default")
      (node (ref "FAULT") (pin "C") (pinfunction "C_C") (pintype "passive"))
      (node (ref "IC4-E-FUSE") (pin "6") (pinfunction "~{FLT}_6") (pintype "tri_state"))
    )
    (net (code "59") (name "Net-(IC5-5V-BYPASS)") (class "Default")
      (node (ref "C53") (pin "2") (pinfunction "2_2") (pintype "passive"))
      (node (ref "IC5-5V") (pin "4") (pinfunction "BYPASS_4") (pintype "input"))
    )
    (net (code "60") (name "Net-(IC6-I-SENSE-VOUT)") (class "Default")
      (node (ref "IC6-I-SENSE") (pin "7") (pinfunction "VOUT_7") (pintype "output"))
      (node (ref "R-I-SENSE-SEL") (pin "2") (pinfunction "2_2") (pintype "passive"))
    )
    (net (code "61") (name "Net-(ILIMIT-P$1)") (class "Default")
      (node (ref "ILIMIT") (pin "1") (pinfunction "P$1_1") (pintype "bidirectional"))
      (node (ref "RILIM1") (pin "2") (pinfunction "2_2") (pintype "passive"))
    )
    (net (code "62") (name "Net-(ILIMIT-P$3)") (class "Default")
      (node (ref "ILIMIT") (pin "3") (pinfunction "P$3_3") (pintype "bidirectional"))
      (node (ref "RILIM2") (pin "2") (pinfunction "2_2") (pintype "passive"))
    )
    (net (code "63") (name "Net-(POW~12V-PadA)") (class "Default")
      (node (ref "POW~12V") (pin "A") (pinfunction "A_A") (pintype "passive"))
      (node (ref "R46") (pin "1") (pinfunction "1_1") (pintype "passive"))
      (node (ref "R47") (pin "2") (pinfunction "2_2") (pintype "passive"))
    )
    (net (code "64") (name "Net-(R3-Pad1)") (class "Default")
      (node (ref "R3") (pin "1") (pinfunction "1_1") (pintype "passive"))
      (node (ref "VIN-ON") (pin "A") (pinfunction "A_A") (pintype "passive"))
    )
    (net (code "65") (name "Net-(R16-Pad1)") (class "Default")
      (node (ref "R16") (pin "1") (pinfunction "1_1") (pintype "passive"))
      (node (ref "R30") (pin "1") (pinfunction "1_1") (pintype "passive"))
      (node (ref "ROTARY-ENCODER") (pin "A") (pinfunction "A_A") (pintype "bidirectional"))
    )
    (net (code "66") (name "Net-(R19-Pad1)") (class "Default")
      (node (ref "R19") (pin "1") (pinfunction "1_1") (pintype "passive"))
      (node (ref "R29") (pin "1") (pinfunction "1_1") (pintype "passive"))
      (node (ref "ROTARY-ENCODER") (pin "B") (pinfunction "B_B") (pintype "bidirectional"))
    )
    (net (code "67") (name "Net-(R22-Pad2)") (class "Default")
      (node (ref "R22") (pin "2") (pinfunction "2_2") (pintype "passive"))
      (node (ref "USB-ON") (pin "C") (pinfunction "C_C") (pintype "passive"))
    )
    (net (code "68") (name "Net-(R32-Pad1)") (class "Default")
      (node (ref "R32") (pin "1") (pinfunction "1_1") (pintype "passive"))
      (node (ref "R33") (pin "2") (pinfunction "2_2") (pintype "passive"))
    )
    (net (code "69") (name "Net-(R32-Pad2)") (class "Default")
      (node (ref "R32") (pin "2") (pinfunction "2_2") (pintype "passive"))
      (node (ref "VBOOST-SEL") (pin "1") (pinfunction "1_1") (pintype "bidirectional"))
    )
    (net (code "70") (name "Net-(R34-Pad2)") (class "Default")
      (node (ref "R34") (pin "2") (pinfunction "2_2") (pintype "passive"))
      (node (ref "VBOOST-SEL") (pin "2") (pinfunction "2_2") (pintype "bidirectional"))
    )
    (net (code "71") (name "Net-(R35-CCW)") (class "Default")
      (node (ref "R34") (pin "1") (pinfunction "1_1") (pintype "passive"))
      (node (ref "R35") (pin "3") (pinfunction "CCW_3") (pintype "passive"))
    )
    (net (code "72") (name "Net-(S2-RT)") (class "Default")
      (node (ref "R2") (pin "1") (pinfunction "1_1") (pintype "passive"))
      (node (ref "S2") (pin "6") (pinfunction "RT_6") (pintype "output"))
    )
    (net (code "73") (name "Net-(S3-B)") (class "Default")
      (node (ref "R36") (pin "1") (pinfunction "1_1") (pintype "passive"))
      (node (ref "S3") (pin "1") (pinfunction "B_1") (pintype "passive"))
    )
    (net (code "74") (name "Net-(USBC-CC1)") (class "Default")
      (node (ref "RD1") (pin "2") (pinfunction "2_2") (pintype "passive"))
      (node (ref "USBC") (pin "A5") (pinfunction "CC1_A5") (pintype "bidirectional"))
    )
    (net (code "75") (name "Net-(USBC-CC2)") (class "Default")
      (node (ref "RD2") (pin "2") (pinfunction "2_2") (pintype "passive"))
      (node (ref "USBC") (pin "B5") (pinfunction "CC2_B5") (pintype "bidirectional"))
    )
    (net (code "76") (name "VIN") (class "Default")
      (node (ref "C31") (pin "2") (pinfunction "2_2") (pintype "passive"))
      (node (ref "D5") (pin "C") (pinfunction "C_C") (pintype "passive"))
      (node (ref "IC3") (pin "4") (pinfunction "EN_4") (pintype "output"))
      (node (ref "IC3") (pin "5") (pinfunction "VIN_5") (pintype "input"))
      (node (ref "L31") (pin "P$1") (pinfunction "P$1_P$1") (pintype "bidirectional"))
      (node (ref "R3") (pin "2") (pinfunction "2_2") (pintype "passive"))
      (node (ref "R4") (pin "1") (pinfunction "1_1") (pintype "passive"))
      (node (ref "R48") (pin "2") (pinfunction "2_2") (pintype "passive"))
      (node (ref "S4") (pin "2") (pinfunction "S_2") (pintype "passive"))
      (node (ref "VIN") (pin "P$1") (pinfunction "P$1_P$1") (pintype "bidirectional"))
      (node (ref "VIN'") (pin "P$1") (pinfunction "P$1_P$1") (pintype "bidirectional"))
    )
    (net (code "77") (name "unconnected-(IC2-CHARGER-TS-Pad1)") (class "Default")
      (node (ref "IC2-CHARGER") (pin "1") (pinfunction "TS_1") (pintype "input"))
    )
    (net (code "78") (name "unconnected-(IC3-NC-Pad6)") (class "Default")
      (node (ref "IC3") (pin "6") (pinfunction "NC_6") (pintype "no_connect"))
    )
    (net (code "79") (name "unconnected-(IC6-I-SENSE-NC-Pad6)") (class "Default")
      (node (ref "IC6-I-SENSE") (pin "6") (pinfunction "NC_6") (pintype "output"))
    )
    (net (code "80") (name "unconnected-(R35-CW-Pad1)") (class "Default")
      (node (ref "R35") (pin "1") (pinfunction "CW_1") (pintype "passive"))
    )
    (net (code "81") (name "unconnected-(USBC-PadSH1)") (class "Default")
      (node (ref "USBC") (pin "SH1") (pinfunction "SH1_SH1") (pintype "bidirectional"))
    )
    (net (code "82") (name "unconnected-(USBC-PadSH2)") (class "Default")
      (node (ref "USBC") (pin "SH2") (pinfunction "SH2_SH2") (pintype "bidirectional"))
    )
    (net (code "83") (name "unconnected-(USBC-PadSH3)") (class "Default")
      (node (ref "USBC") (pin "SH3") (pinfunction "SH3_SH3") (pintype "bidirectional"))
    )
    (net (code "84") (name "unconnected-(USBC-PadSH4)") (class "Default")
      (node (ref "USBC") (pin "SH4") (pinfunction "SH4_SH4") (pintype "bidirectional"))
    )
  )
)
